# STLink_V3E_PWR.net
KiCad netlist of a schematic drawn in Altium Designer
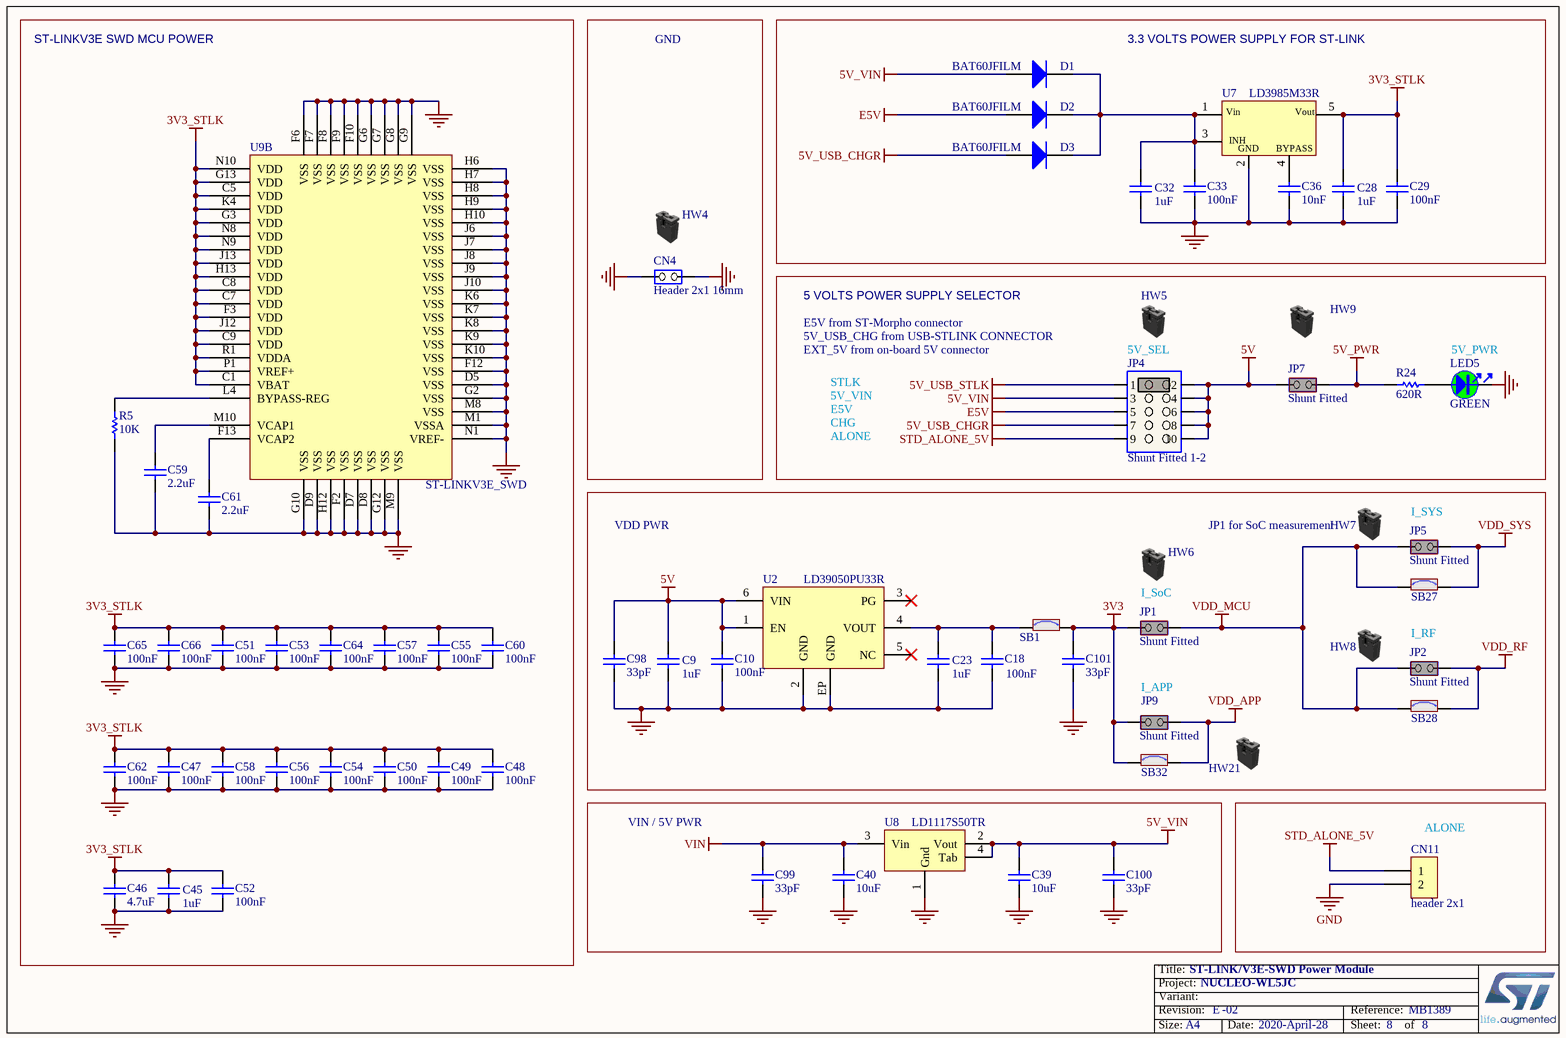
[diagram p0: STLink_V3E_PWR.SchDoc]

(export (version "E")
  (design (tool "Eeschema 10.0.6"))
  (components
    (comp (ref "C9")
      (value "1uF")
      (footprint "C0603")
      (description "Capacitor, MLCC, 1uF, 16V, X5R, 10%, 0603, T=0,8mm")
      (fields
        (field (name "INTERNAL_PART_NUMBER") "MCD-00010")
        (field (name "MANUFACTURER_PART_NUMBER") "CC0603KRX5R7BB105")
        (field (name "PROVIDED_BY") "SUBCO")
      )
      (libsource (lib "MCD_PARTS_database") (part "Capacitor"))
    )
    (comp (ref "C10")
      (value "100nF")
      (footprint "C0402")
      (description "Capacitor, MLCC, 100nF, 16V, X7R, 10%, 0402, T=0,5mm")
      (fields
        (field (name "INTERNAL_PART_NUMBER") "MCD-00102")
        (field (name "MANUFACTURER_PART_NUMBER") "CC0402KRX7R7BB104")
        (field (name "PROVIDED_BY") "SUBCO")
      )
      (libsource (lib "MCD_PARTS_database") (part "Capacitor"))
    )
    (comp (ref "C18")
      (value "100nF")
      (footprint "C0402")
      (description "Capacitor, MLCC, 100nF, 16V, X7R, 10%, 0402, T=0,5mm")
      (fields
        (field (name "INTERNAL_PART_NUMBER") "MCD-00102")
        (field (name "MANUFACTURER_PART_NUMBER") "CC0402KRX7R7BB104")
        (field (name "PROVIDED_BY") "SUBCO")
      )
      (libsource (lib "MCD_PARTS_database") (part "Capacitor"))
    )
    (comp (ref "C23")
      (value "1uF")
      (footprint "C0603")
      (description "Capacitor, MLCC, 1uF, 16V, X5R, 10%, 0603, T=0,8mm")
      (fields
        (field (name "INTERNAL_PART_NUMBER") "MCD-00010")
        (field (name "MANUFACTURER_PART_NUMBER") "CC0603KRX5R7BB105")
        (field (name "PROVIDED_BY") "SUBCO")
      )
      (libsource (lib "MCD_PARTS_database") (part "Capacitor"))
    )
    (comp (ref "C28")
      (value "1uF")
      (footprint "C0603")
      (description "Capacitor, MLCC, 1uF, 16V, X5R, 10%, 0603, T=0,8mm")
      (fields
        (field (name "INTERNAL_PART_NUMBER") "MCD-00010")
        (field (name "MANUFACTURER_PART_NUMBER") "CC0603KRX5R7BB105")
        (field (name "PROVIDED_BY") "SUBCO")
      )
      (libsource (lib "MCD_PARTS_database") (part "Capacitor"))
    )
    (comp (ref "C29")
      (value "100nF")
      (footprint "C0402")
      (description "Capacitor, MLCC, 100nF, 16V, X7R, 10%, 0402, T=0,5mm")
      (fields
        (field (name "INTERNAL_PART_NUMBER") "MCD-00102")
        (field (name "MANUFACTURER_PART_NUMBER") "CC0402KRX7R7BB104")
        (field (name "PROVIDED_BY") "SUBCO")
      )
      (libsource (lib "MCD_PARTS_database") (part "Capacitor"))
    )
    (comp (ref "C32")
      (value "1uF")
      (footprint "C0603")
      (description "Capacitor, MLCC, 1uF, 16V, X5R, 10%, 0603, T=0,8mm")
      (fields
        (field (name "INTERNAL_PART_NUMBER") "MCD-00010")
        (field (name "MANUFACTURER_PART_NUMBER") "CC0603KRX5R7BB105")
        (field (name "PROVIDED_BY") "SUBCO")
      )
      (libsource (lib "MCD_PARTS_database") (part "Capacitor"))
    )
    (comp (ref "C33")
      (value "100nF")
      (footprint "C0402")
      (description "Capacitor, MLCC, 100nF, 16V, X7R, 10%, 0402, T=0,5mm")
      (fields
        (field (name "INTERNAL_PART_NUMBER") "MCD-00102")
        (field (name "MANUFACTURER_PART_NUMBER") "CC0402KRX7R7BB104")
        (field (name "PROVIDED_BY") "SUBCO")
      )
      (libsource (lib "MCD_PARTS_database") (part "Capacitor"))
    )
    (comp (ref "C36")
      (value "10nF")
      (footprint "C0402")
      (description "Capacitor, MLCC, 10nF, 16V, X7R, 10%, 0402, T=0.5mm")
      (fields
        (field (name "INTERNAL_PART_NUMBER") "MCD-00011")
        (field (name "MANUFACTURER_PART_NUMBER") "CC0402KRX7R7BB103")
        (field (name "PROVIDED_BY") "SUBCO")
      )
      (libsource (lib "MCD_PARTS_database") (part "Capacitor"))
    )
    (comp (ref "C39")
      (value "10uF")
      (footprint "C0805")
      (description "Capacitor, MLCC, 10uF, 25V, X5R, 10%, 0805, T=0,85mm")
      (fields
        (field (name "INTERNAL_PART_NUMBER") "MCD-00014")
        (field (name "MANUFACTURER_PART_NUMBER") "CC0805KRX5R8BB106")
        (field (name "PROVIDED_BY") "SUBCO")
      )
      (libsource (lib "MCD_PARTS_database") (part "Capacitor"))
    )
    (comp (ref "C40")
      (value "10uF")
      (footprint "C0805")
      (description "Capacitor, MLCC, 10uF, 25V, X5R, 10%, 0805, T=0,85mm")
      (fields
        (field (name "INTERNAL_PART_NUMBER") "MCD-00014")
        (field (name "MANUFACTURER_PART_NUMBER") "CC0805KRX5R8BB106")
        (field (name "PROVIDED_BY") "SUBCO")
      )
      (libsource (lib "MCD_PARTS_database") (part "Capacitor"))
    )
    (comp (ref "C45")
      (value "1uF")
      (footprint "C0603")
      (description "Capacitor, MLCC, 1uF, 16V, X5R, 10%, 0603, T=0,8mm")
      (fields
        (field (name "INTERNAL_PART_NUMBER") "MCD-00010")
        (field (name "MANUFACTURER_PART_NUMBER") "CC0603KRX5R7BB105")
        (field (name "PROVIDED_BY") "SUBCO")
      )
      (libsource (lib "MCD_PARTS_database") (part "Capacitor"))
    )
    (comp (ref "C46")
      (value "4.7uF")
      (footprint "C0603")
      (description "Capacitor, MLCC, 4.7uF, 16V, X5R, 10%, 0603, T=0.8mm")
      (fields
        (field (name "INTERNAL_PART_NUMBER") "MCD-00009")
        (field (name "MANUFACTURER_PART_NUMBER") "CC0603KRX5R7BB475")
        (field (name "PROVIDED_BY") "SUBCO")
      )
      (libsource (lib "MCD_PARTS_database") (part "Capacitor"))
    )
    (comp (ref "C47")
      (value "100nF")
      (footprint "C0402")
      (description "Capacitor, MLCC, 100nF, 16V, X7R, 10%, 0402, T=0,5mm")
      (fields
        (field (name "INTERNAL_PART_NUMBER") "MCD-00102")
        (field (name "MANUFACTURER_PART_NUMBER") "CC0402KRX7R7BB104")
        (field (name "PROVIDED_BY") "SUBCO")
      )
      (libsource (lib "MCD_PARTS_database") (part "Capacitor"))
    )
    (comp (ref "C48")
      (value "100nF")
      (footprint "C0402")
      (description "Capacitor, MLCC, 100nF, 16V, X7R, 10%, 0402, T=0,5mm")
      (fields
        (field (name "INTERNAL_PART_NUMBER") "MCD-00102")
        (field (name "MANUFACTURER_PART_NUMBER") "CC0402KRX7R7BB104")
        (field (name "PROVIDED_BY") "SUBCO")
      )
      (libsource (lib "MCD_PARTS_database") (part "Capacitor"))
    )
    (comp (ref "C49")
      (value "100nF")
      (footprint "C0402")
      (description "Capacitor, MLCC, 100nF, 16V, X7R, 10%, 0402, T=0,5mm")
      (fields
        (field (name "INTERNAL_PART_NUMBER") "MCD-00102")
        (field (name "MANUFACTURER_PART_NUMBER") "CC0402KRX7R7BB104")
        (field (name "PROVIDED_BY") "SUBCO")
      )
      (libsource (lib "MCD_PARTS_database") (part "Capacitor"))
    )
    (comp (ref "C50")
      (value "100nF")
      (footprint "C0402")
      (description "Capacitor, MLCC, 100nF, 16V, X7R, 10%, 0402, T=0,5mm")
      (fields
        (field (name "INTERNAL_PART_NUMBER") "MCD-00102")
        (field (name "MANUFACTURER_PART_NUMBER") "CC0402KRX7R7BB104")
        (field (name "PROVIDED_BY") "SUBCO")
      )
      (libsource (lib "MCD_PARTS_database") (part "Capacitor"))
    )
    (comp (ref "C51")
      (value "100nF")
      (footprint "C0402")
      (description "Capacitor, MLCC, 100nF, 16V, X7R, 10%, 0402, T=0,5mm")
      (fields
        (field (name "INTERNAL_PART_NUMBER") "MCD-00102")
        (field (name "MANUFACTURER_PART_NUMBER") "CC0402KRX7R7BB104")
        (field (name "PROVIDED_BY") "SUBCO")
      )
      (libsource (lib "MCD_PARTS_database") (part "Capacitor"))
    )
    (comp (ref "C52")
      (value "100nF")
      (footprint "C0402")
      (description "Capacitor, MLCC, 100nF, 16V, X7R, 10%, 0402, T=0,5mm")
      (fields
        (field (name "INTERNAL_PART_NUMBER") "MCD-00102")
        (field (name "MANUFACTURER_PART_NUMBER") "CC0402KRX7R7BB104")
        (field (name "PROVIDED_BY") "SUBCO")
      )
      (libsource (lib "MCD_PARTS_database") (part "Capacitor"))
    )
    (comp (ref "C53")
      (value "100nF")
      (footprint "C0402")
      (description "Capacitor, MLCC, 100nF, 16V, X7R, 10%, 0402, T=0,5mm")
      (fields
        (field (name "INTERNAL_PART_NUMBER") "MCD-00102")
        (field (name "MANUFACTURER_PART_NUMBER") "CC0402KRX7R7BB104")
        (field (name "PROVIDED_BY") "SUBCO")
      )
      (libsource (lib "MCD_PARTS_database") (part "Capacitor"))
    )
    (comp (ref "C54")
      (value "100nF")
      (footprint "C0402")
      (description "Capacitor, MLCC, 100nF, 16V, X7R, 10%, 0402, T=0,5mm")
      (fields
        (field (name "INTERNAL_PART_NUMBER") "MCD-00102")
        (field (name "MANUFACTURER_PART_NUMBER") "CC0402KRX7R7BB104")
        (field (name "PROVIDED_BY") "SUBCO")
      )
      (libsource (lib "MCD_PARTS_database") (part "Capacitor"))
    )
    (comp (ref "C55")
      (value "100nF")
      (footprint "C0402")
      (description "Capacitor, MLCC, 100nF, 16V, X7R, 10%, 0402, T=0,5mm")
      (fields
        (field (name "INTERNAL_PART_NUMBER") "MCD-00102")
        (field (name "MANUFACTURER_PART_NUMBER") "CC0402KRX7R7BB104")
        (field (name "PROVIDED_BY") "SUBCO")
      )
      (libsource (lib "MCD_PARTS_database") (part "Capacitor"))
    )
    (comp (ref "C56")
      (value "100nF")
      (footprint "C0402")
      (description "Capacitor, MLCC, 100nF, 16V, X7R, 10%, 0402, T=0,5mm")
      (fields
        (field (name "INTERNAL_PART_NUMBER") "MCD-00102")
        (field (name "MANUFACTURER_PART_NUMBER") "CC0402KRX7R7BB104")
        (field (name "PROVIDED_BY") "SUBCO")
      )
      (libsource (lib "MCD_PARTS_database") (part "Capacitor"))
    )
    (comp (ref "C57")
      (value "100nF")
      (footprint "C0402")
      (description "Capacitor, MLCC, 100nF, 16V, X7R, 10%, 0402, T=0,5mm")
      (fields
        (field (name "INTERNAL_PART_NUMBER") "MCD-00102")
        (field (name "MANUFACTURER_PART_NUMBER") "CC0402KRX7R7BB104")
        (field (name "PROVIDED_BY") "SUBCO")
      )
      (libsource (lib "MCD_PARTS_database") (part "Capacitor"))
    )
    (comp (ref "C58")
      (value "100nF")
      (footprint "C0402")
      (description "Capacitor, MLCC, 100nF, 16V, X7R, 10%, 0402, T=0,5mm")
      (fields
        (field (name "INTERNAL_PART_NUMBER") "MCD-00102")
        (field (name "MANUFACTURER_PART_NUMBER") "CC0402KRX7R7BB104")
        (field (name "PROVIDED_BY") "SUBCO")
      )
      (libsource (lib "MCD_PARTS_database") (part "Capacitor"))
    )
    (comp (ref "C59")
      (value "2.2uF")
      (footprint "C0603")
      (description "Capacitor, MLCC, 2.2uF, 10V, X5R, 10%, 0603, T=0,8mm")
      (fields
        (field (name "INTERNAL_PART_NUMBER") "MCD-00012")
        (field (name "MANUFACTURER_PART_NUMBER") "CC0603KRX5R6BB225")
        (field (name "PROVIDED_BY") "SUBCO")
      )
      (libsource (lib "MCD_PARTS_database") (part "Capacitor"))
    )
    (comp (ref "C60")
      (value "100nF")
      (footprint "C0402")
      (description "Capacitor, MLCC, 100nF, 16V, X7R, 10%, 0402, T=0,5mm")
      (fields
        (field (name "INTERNAL_PART_NUMBER") "MCD-00102")
        (field (name "MANUFACTURER_PART_NUMBER") "CC0402KRX7R7BB104")
        (field (name "PROVIDED_BY") "SUBCO")
      )
      (libsource (lib "MCD_PARTS_database") (part "Capacitor"))
    )
    (comp (ref "C61")
      (value "2.2uF")
      (footprint "C0603")
      (description "Capacitor, MLCC, 2.2uF, 10V, X5R, 10%, 0603, T=0,8mm")
      (fields
        (field (name "INTERNAL_PART_NUMBER") "MCD-00012")
        (field (name "MANUFACTURER_PART_NUMBER") "CC0603KRX5R6BB225")
        (field (name "PROVIDED_BY") "SUBCO")
      )
      (libsource (lib "MCD_PARTS_database") (part "Capacitor"))
    )
    (comp (ref "C62")
      (value "100nF")
      (footprint "C0402")
      (description "Capacitor, MLCC, 100nF, 16V, X7R, 10%, 0402, T=0,5mm")
      (fields
        (field (name "INTERNAL_PART_NUMBER") "MCD-00102")
        (field (name "MANUFACTURER_PART_NUMBER") "CC0402KRX7R7BB104")
        (field (name "PROVIDED_BY") "SUBCO")
      )
      (libsource (lib "MCD_PARTS_database") (part "Capacitor"))
    )
    (comp (ref "C64")
      (value "100nF")
      (footprint "C0402")
      (description "Capacitor, MLCC, 100nF, 16V, X7R, 10%, 0402, T=0,5mm")
      (fields
        (field (name "INTERNAL_PART_NUMBER") "MCD-00102")
        (field (name "MANUFACTURER_PART_NUMBER") "CC0402KRX7R7BB104")
        (field (name "PROVIDED_BY") "SUBCO")
      )
      (libsource (lib "MCD_PARTS_database") (part "Capacitor"))
    )
    (comp (ref "C65")
      (value "100nF")
      (footprint "C0402")
      (description "Capacitor, MLCC, 100nF, 16V, X7R, 10%, 0402, T=0,5mm")
      (fields
        (field (name "INTERNAL_PART_NUMBER") "MCD-00102")
        (field (name "MANUFACTURER_PART_NUMBER") "CC0402KRX7R7BB104")
        (field (name "PROVIDED_BY") "SUBCO")
      )
      (libsource (lib "MCD_PARTS_database") (part "Capacitor"))
    )
    (comp (ref "C66")
      (value "100nF")
      (footprint "C0402")
      (description "Capacitor, MLCC, 100nF, 16V, X7R, 10%, 0402, T=0,5mm")
      (fields
        (field (name "INTERNAL_PART_NUMBER") "MCD-00102")
        (field (name "MANUFACTURER_PART_NUMBER") "CC0402KRX7R7BB104")
        (field (name "PROVIDED_BY") "SUBCO")
      )
      (libsource (lib "MCD_PARTS_database") (part "Capacitor"))
    )
    (comp (ref "C98")
      (value "33pF")
      (footprint "C0402")
      (description "Capacitor, MLCC, 33pF, 50V, NPO, +/-2%, 0402, T=0,5mm")
      (fields
        (field (name "INTERNAL_PART_NUMBER") "MCD-01784")
        (field (name "MANUFACTURER_PART_NUMBER") "CC0402GRNPO9BN330")
        (field (name "PROVIDED_BY") "SUBCO")
      )
      (libsource (lib "MCD_PARTS_database") (part "Capacitor"))
    )
    (comp (ref "C99")
      (value "33pF")
      (footprint "C0402")
      (description "Capacitor, MLCC, 33pF, 50V, NPO, +/-2%, 0402, T=0,5mm")
      (fields
        (field (name "INTERNAL_PART_NUMBER") "MCD-01784")
        (field (name "MANUFACTURER_PART_NUMBER") "CC0402GRNPO9BN330")
        (field (name "PROVIDED_BY") "SUBCO")
      )
      (libsource (lib "MCD_PARTS_database") (part "Capacitor"))
    )
    (comp (ref "C100")
      (value "33pF")
      (footprint "C0402")
      (description "Capacitor, MLCC, 33pF, 50V, NPO, +/-2%, 0402, T=0,5mm")
      (fields
        (field (name "INTERNAL_PART_NUMBER") "MCD-01784")
        (field (name "MANUFACTURER_PART_NUMBER") "CC0402GRNPO9BN330")
        (field (name "PROVIDED_BY") "SUBCO")
      )
      (libsource (lib "MCD_PARTS_database") (part "Capacitor"))
    )
    (comp (ref "C101")
      (value "33pF")
      (footprint "C0402")
      (description "Capacitor, MLCC, 33pF, 50V, NPO, +/-2%, 0402, T=0,5mm")
      (fields
        (field (name "INTERNAL_PART_NUMBER") "MCD-01784")
        (field (name "MANUFACTURER_PART_NUMBER") "CC0402GRNPO9BN330")
        (field (name "PROVIDED_BY") "SUBCO")
      )
      (libsource (lib "MCD_PARTS_database") (part "Capacitor"))
    )
    (comp (ref "CN4")
      (value "Header 2x1 16mm")
      (footprint "CON_SAMTEC_TSW-102-09-X-S")
      (description "Header, 2x1, 2,54mm, VR, TH, Height 5.84mm/10.16mm")
      (fields
        (field (name "INTERNAL_PART_NUMBER") "MCD-00214")
        (field (name "MANUFACTURER_PART_NUMBER") "TSW-102-09-x-S")
        (field (name "PROVIDED_BY") "SUBCO")
      )
      (libsource (lib "MCD_PARTS_database") (part "Jumper_Header 2x1"))
    )
    (comp (ref "CN11")
      (value "header 2x1")
      (footprint "CON_988-JIUBABA_PHFS25-11-02-G0B115-T-1")
      (description "Header, 2x1, 2.54mm, VR, TH, Height 6mm/3mm")
      (fields
        (field (name "INTERNAL_PART_NUMBER") "MCD-00314")
        (field (name "MANUFACTURER_PART_NUMBER") "PHFS25-11-02-G0B115-T-1")
        (field (name "PROVIDED_BY") "SUBCO")
      )
      (libsource (lib "MCD_PARTS_database") (part "Header 2x1"))
    )
    (comp (ref "D1")
      (value "BAT60JFILM")
      (footprint "DIO_SOD323")
      (fields
        (field (name "INTERNAL_PART_NUMBER") "MCD-00034")
        (field (name "MANUFACTURER") "STMICROELECTRONICS")
        (field (name "BMS_PART_NUMBER") "9151097")
        (field (name "PROVIDED_BY") "SUBCO with ST control")
      )
      (libsource (lib "MCD_PARTS_database") (part "BAT60JFILM"))
    )
    (comp (ref "D2")
      (value "BAT60JFILM")
      (footprint "DIO_SOD323")
      (fields
        (field (name "INTERNAL_PART_NUMBER") "MCD-00034")
        (field (name "MANUFACTURER") "STMICROELECTRONICS")
        (field (name "BMS_PART_NUMBER") "9151097")
        (field (name "PROVIDED_BY") "SUBCO with ST control")
      )
      (libsource (lib "MCD_PARTS_database") (part "BAT60JFILM"))
    )
    (comp (ref "D3")
      (value "BAT60JFILM")
      (footprint "DIO_SOD323")
      (fields
        (field (name "INTERNAL_PART_NUMBER") "MCD-00034")
        (field (name "MANUFACTURER") "STMICROELECTRONICS")
        (field (name "BMS_PART_NUMBER") "9151097")
        (field (name "PROVIDED_BY") "SUBCO with ST control")
      )
      (libsource (lib "MCD_PARTS_database") (part "BAT60JFILM"))
    )
    (comp (ref "HW4")
      (value "~")
      (description "SHUNT 2.54mm BLACK")
      (fields
        (field (name "INTERNAL_PART_NUMBER") "MCD-00043")
        (field (name "MANUFACTURER_PART_NUMBER") "SNT-100-BK-G")
        (field (name "PROVIDED_BY") "SUBCO")
      )
      (libsource (lib "MCD_PARTS_database") (part "Shunt Black 2.54mm"))
    )
    (comp (ref "HW5")
      (value "~")
      (description "SHUNT 2.54mm BLACK")
      (fields
        (field (name "INTERNAL_PART_NUMBER") "MCD-00043")
        (field (name "MANUFACTURER_PART_NUMBER") "SNT-100-BK-G")
        (field (name "PROVIDED_BY") "SUBCO")
      )
      (libsource (lib "MCD_PARTS_database") (part "Shunt Black 2.54mm"))
    )
    (comp (ref "HW6")
      (value "~")
      (description "SHUNT 2.54mm BLACK")
      (fields
        (field (name "INTERNAL_PART_NUMBER") "MCD-00043")
        (field (name "MANUFACTURER_PART_NUMBER") "SNT-100-BK-G")
        (field (name "PROVIDED_BY") "SUBCO")
      )
      (libsource (lib "MCD_PARTS_database") (part "Shunt Black 2.54mm"))
    )
    (comp (ref "HW7")
      (value "~")
      (description "SHUNT 2.54mm BLACK")
      (fields
        (field (name "INTERNAL_PART_NUMBER") "MCD-00043")
        (field (name "MANUFACTURER_PART_NUMBER") "SNT-100-BK-G")
        (field (name "PROVIDED_BY") "SUBCO")
      )
      (libsource (lib "MCD_PARTS_database") (part "Shunt Black 2.54mm"))
    )
    (comp (ref "HW8")
      (value "~")
      (description "SHUNT 2.54mm BLACK")
      (fields
        (field (name "INTERNAL_PART_NUMBER") "MCD-00043")
        (field (name "MANUFACTURER_PART_NUMBER") "SNT-100-BK-G")
        (field (name "PROVIDED_BY") "SUBCO")
      )
      (libsource (lib "MCD_PARTS_database") (part "Shunt Black 2.54mm"))
    )
    (comp (ref "HW9")
      (value "~")
      (description "SHUNT 2.54mm BLACK")
      (fields
        (field (name "INTERNAL_PART_NUMBER") "MCD-00043")
        (field (name "MANUFACTURER_PART_NUMBER") "SNT-100-BK-G")
        (field (name "PROVIDED_BY") "SUBCO")
      )
      (libsource (lib "MCD_PARTS_database") (part "Shunt Black 2.54mm"))
    )
    (comp (ref "HW21")
      (value "~")
      (description "SHUNT 2.54mm BLACK")
      (fields
        (field (name "INTERNAL_PART_NUMBER") "MCD-00043")
        (field (name "MANUFACTURER_PART_NUMBER") "SNT-100-BK-G")
        (field (name "PROVIDED_BY") "SUBCO")
      )
      (libsource (lib "MCD_PARTS_database") (part "Shunt Black 2.54mm"))
    )
    (comp (ref "JP1")
      (value "Shunt Fitted")
      (footprint "CON_SAMTEC_TSW-102-07-G-S")
      (description "Header, 2x1, 2,54mm, VR, TH, Height 5.84mm/2.54mm - Shunt Fitted by default")
      (fields
        (field (name "INTERNAL_PART_NUMBER") "MCD-00683")
        (field (name "MANUFACTURER_PART_NUMBER") "TSW-102-07-x-S")
        (field (name "PROVIDED_BY") "SUBCO")
      )
      (libsource (lib "MCD_PARTS_database") (part "Jumper_Header 2x1 Fitted"))
    )
    (comp (ref "JP2")
      (value "Shunt Fitted")
      (footprint "CON_SAMTEC_TSW-102-07-G-S")
      (description "Header, 2x1, 2,54mm, VR, TH, Height 5.84mm/2.54mm - Shunt Fitted by default")
      (fields
        (field (name "INTERNAL_PART_NUMBER") "MCD-00683")
        (field (name "MANUFACTURER_PART_NUMBER") "TSW-102-07-x-S")
        (field (name "PROVIDED_BY") "SUBCO")
      )
      (libsource (lib "MCD_PARTS_database") (part "Jumper_Header 2x1 Fitted"))
    )
    (comp (ref "JP4")
      (value "Shunt Fitted 1-2")
      (footprint "CON_SAMTEC_TSW-105-07-X-D")
      (description "Header, 5x2, 2,54mm, VR, TH, Height 5.84mm/2.54mm - Shunt Fitted 1-2")
      (fields
        (field (name "INTERNAL_PART_NUMBER") "MCD-01203")
        (field (name "MANUFACTURER_PART_NUMBER") "TSW-105-07-x-D")
        (field (name "PROVIDED_BY") "SUBCO")
      )
      (libsource (lib "MCD_PARTS_database") (part "Jumper_Header 5x2 Fitted 1-2"))
    )
    (comp (ref "JP5")
      (value "Shunt Fitted")
      (footprint "CON_SAMTEC_TSW-102-07-G-S")
      (description "Header, 2x1, 2,54mm, VR, TH, Height 5.84mm/2.54mm - Shunt Fitted by default")
      (fields
        (field (name "INTERNAL_PART_NUMBER") "MCD-00683")
        (field (name "MANUFACTURER_PART_NUMBER") "TSW-102-07-x-S")
        (field (name "PROVIDED_BY") "SUBCO")
      )
      (libsource (lib "MCD_PARTS_database") (part "Jumper_Header 2x1 Fitted"))
    )
    (comp (ref "JP7")
      (value "Shunt Fitted")
      (footprint "CON_SAMTEC_TSW-102-07-G-S")
      (description "Header, 2x1, 2,54mm, VR, TH, Height 5.84mm/2.54mm - Shunt Fitted by default")
      (fields
        (field (name "INTERNAL_PART_NUMBER") "MCD-00683")
        (field (name "MANUFACTURER_PART_NUMBER") "TSW-102-07-x-S")
        (field (name "PROVIDED_BY") "SUBCO")
      )
      (libsource (lib "MCD_PARTS_database") (part "Jumper_Header 2x1 Fitted"))
    )
    (comp (ref "JP9")
      (value "Shunt Fitted")
      (footprint "CON_SAMTEC_TSW-102-07-G-S")
      (description "Header, 2x1, 2,54mm, VR, TH, Height 5.84mm/2.54mm - Shunt Fitted by default")
      (fields
        (field (name "INTERNAL_PART_NUMBER") "MCD-00683")
        (field (name "MANUFACTURER_PART_NUMBER") "TSW-102-07-x-S")
        (field (name "PROVIDED_BY") "SUBCO")
      )
      (libsource (lib "MCD_PARTS_database") (part "Jumper_Header 2x1 Fitted"))
    )
    (comp (ref "LED5")
      (value "GREEN")
      (footprint "LED_0603_OSRAM_LG-Q396-PS-35_GREEN_1A2K_H0P4")
      (description "LED Green, 0603 SMD, Forward Voltage Typ=2V, Max=2.5V")
      (fields
        (field (name "INTERNAL_PART_NUMBER") "MCD-00588")
        (field (name "MANUFACTURER_PART_NUMBER") "LG Q396-PS-35")
        (field (name "PROVIDED_BY") "SUBCO")
      )
      (libsource (lib "MCD_PARTS_database") (part "LED_green"))
    )
    (comp (ref "R5")
      (value "10K")
      (footprint "R0402")
      (description "Resistor,10K,0402,1%,1/16W")
      (fields
        (field (name "INTERNAL_PART_NUMBER") "MCD-00053")
        (field (name "MANUFACTURER_PART_NUMBER") "RC0402FR-0710KL")
        (field (name "PROVIDED_BY") "SUBCO")
      )
      (libsource (lib "MCD_PARTS_database") (part "Resistor"))
    )
    (comp (ref "R24")
      (value "620R")
      (footprint "R0402")
      (description "Resistor,620R,0402,1%,1/16W")
      (fields
        (field (name "INTERNAL_PART_NUMBER") "MCD-00499")
        (field (name "MANUFACTURER_PART_NUMBER") "RC0402FR-07620RL")
        (field (name "PROVIDED_BY") "SUBCO")
      )
      (libsource (lib "MCD_PARTS_database") (part "Resistor"))
    )
    (comp (ref "SB1")
      (value "~")
      (footprint "SOLDER-BRIDGE_R0603-0R")
      (description "Solder Bridge ON")
      (fields
        (field (name "INTERNAL_PART_NUMBER") "MCD-00071")
        (field (name "MANUFACTURER_PART_NUMBER") "RC0603JR-070RL")
        (field (name "PROVIDED_BY") "SUBCO")
      )
      (libsource (lib "MCD_PARTS_database") (part "SB_ON"))
    )
    (comp (ref "SB27")
      (value "~")
      (footprint "SOLDER-BRIDGE_R0603-0R")
      (description "Solder Bridge ON")
      (fields
        (field (name "INTERNAL_PART_NUMBER") "MCD-00071")
        (field (name "MANUFACTURER_PART_NUMBER") "RC0603JR-070RL")
        (field (name "PROVIDED_BY") "SUBCO")
      )
      (libsource (lib "MCD_PARTS_database") (part "SB_ON"))
    )
    (comp (ref "SB28")
      (value "~")
      (footprint "SOLDER-BRIDGE_R0603-0R")
      (description "Solder Bridge ON")
      (fields
        (field (name "INTERNAL_PART_NUMBER") "MCD-00071")
        (field (name "MANUFACTURER_PART_NUMBER") "RC0603JR-070RL")
        (field (name "PROVIDED_BY") "SUBCO")
      )
      (libsource (lib "MCD_PARTS_database") (part "SB_ON"))
    )
    (comp (ref "SB32")
      (value "~")
      (footprint "SOLDER-BRIDGE_R0603-0R")
      (description "Solder Bridge ON")
      (fields
        (field (name "INTERNAL_PART_NUMBER") "MCD-00071")
        (field (name "MANUFACTURER_PART_NUMBER") "RC0603JR-070RL")
        (field (name "PROVIDED_BY") "SUBCO")
      )
      (libsource (lib "MCD_PARTS_database") (part "SB_ON"))
    )
    (comp (ref "U2")
      (value "LD39050PU33R")
      (footprint "ICC_DFN6-EPAD_3X3_P095")
      (description "Low quiescent current and low noise voltage regulators")
      (fields
        (field (name "INTERNAL_PART_NUMBER") "MCD-00215")
        (field (name "MANUFACTURER") "STMICROELECTRONICS")
        (field (name "PROVIDED_BY") "SUBCO with ST control")
      )
      (libsource (lib "MCD_PARTS_database") (part "LD39050PU33R"))
    )
    (comp (ref "U7")
      (value "LD3985M33R")
      (footprint "REG_SOT23-5L")
      (description "Ultra low drop-low noise BiCMOS voltage, regulators low ESR capacitors compatible")
      (fields
        (field (name "INTERNAL_PART_NUMBER") "MCD-00086")
        (field (name "MANUFACTURER") "STMICROELECTRONICS")
        (field (name "PROVIDED_BY") "SUBCO with ST control")
      )
      (libsource (lib "MCD_PARTS_database") (part "LD3985M33R"))
    )
    (comp (ref "U8")
      (value "LD1117S50TR")
      (footprint "REG_SOT223-TAB")
      (description "IC REG LDO 5V 0.8A SOT223")
      (fields
        (field (name "INTERNAL_PART_NUMBER") "MCD-00088")
        (field (name "MANUFACTURER") "STMICROELECTRONICS")
        (field (name "PROVIDED_BY") "SUBCO with ST control")
      )
      (libsource (lib "MCD_PARTS_database") (part "LD1117S50TR"))
    )
    (comp (ref "U9")
      (value "ST-LINKV3E_SWD")
      (footprint "ICC_UFBGA201_176+25_10X10_P065")
      (description "STM32F723IEK  (STM32F7) BGA176")
      (fields
        (field (name "INTERNAL_PART_NUMBER") "MCD-00596")
        (field (name "MANUFACTURER_PART_NUMBER") "STM32F723IEK6")
        (field (name "PROVIDED_BY") "SUBCO with ST control")
      )
      (libsource (lib "MCD_PARTS_database") (part "ST-LINKV3E_SWD"))
    )
  )
  (nets
    (net (code "1") (name "3V3") (class "Default")
      (node (ref "C101") (pin "2") (pinfunction "2_2") (pintype "passive"))
      (node (ref "JP1") (pin "1") (pinfunction "COMMON_1") (pintype "passive"))
      (node (ref "JP9") (pin "1") (pinfunction "COMMON_1") (pintype "passive"))
      (node (ref "SB1") (pin "2") (pinfunction "2_2") (pintype "passive"))
      (node (ref "SB32") (pin "1") (pinfunction "1_1") (pintype "passive"))
    )
    (net (code "2") (name "3V3_STLK") (class "Default")
      (node (ref "C28") (pin "2") (pinfunction "2_2") (pintype "passive"))
      (node (ref "C29") (pin "2") (pinfunction "2_2") (pintype "passive"))
      (node (ref "C45") (pin "2") (pinfunction "2_2") (pintype "passive"))
      (node (ref "C46") (pin "2") (pinfunction "2_2") (pintype "passive"))
      (node (ref "C47") (pin "2") (pinfunction "2_2") (pintype "passive"))
      (node (ref "C48") (pin "2") (pinfunction "2_2") (pintype "passive"))
      (node (ref "C49") (pin "2") (pinfunction "2_2") (pintype "passive"))
      (node (ref "C50") (pin "2") (pinfunction "2_2") (pintype "passive"))
      (node (ref "C51") (pin "2") (pinfunction "2_2") (pintype "passive"))
      (node (ref "C52") (pin "2") (pinfunction "2_2") (pintype "passive"))
      (node (ref "C53") (pin "2") (pinfunction "2_2") (pintype "passive"))
      (node (ref "C54") (pin "2") (pinfunction "2_2") (pintype "passive"))
      (node (ref "C55") (pin "2") (pinfunction "2_2") (pintype "passive"))
      (node (ref "C56") (pin "2") (pinfunction "2_2") (pintype "passive"))
      (node (ref "C57") (pin "2") (pinfunction "2_2") (pintype "passive"))
      (node (ref "C58") (pin "2") (pinfunction "2_2") (pintype "passive"))
      (node (ref "C60") (pin "2") (pinfunction "2_2") (pintype "passive"))
      (node (ref "C62") (pin "2") (pinfunction "2_2") (pintype "passive"))
      (node (ref "C64") (pin "2") (pinfunction "2_2") (pintype "passive"))
      (node (ref "C65") (pin "2") (pinfunction "2_2") (pintype "passive"))
      (node (ref "C66") (pin "2") (pinfunction "2_2") (pintype "passive"))
      (node (ref "U7") (pin "5") (pinfunction "Vout_5") (pintype "passive"))
      (node (ref "U9") (pin "C1") (pinfunction "VBAT_C1") (pintype "passive"))
      (node (ref "U9") (pin "C5") (pinfunction "VDD_C5") (pintype "passive"))
      (node (ref "U9") (pin "C7") (pinfunction "VDD_C7") (pintype "passive"))
      (node (ref "U9") (pin "C8") (pinfunction "VDD_C8") (pintype "passive"))
      (node (ref "U9") (pin "C9") (pinfunction "VDD_C9") (pintype "passive"))
      (node (ref "U9") (pin "F3") (pinfunction "VDD_F3") (pintype "passive"))
      (node (ref "U9") (pin "G13") (pinfunction "VDD_G13") (pintype "passive"))
      (node (ref "U9") (pin "G3") (pinfunction "VDD_G3") (pintype "passive"))
      (node (ref "U9") (pin "H13") (pinfunction "VDD_H13") (pintype "passive"))
      (node (ref "U9") (pin "J12") (pinfunction "VDD_J12") (pintype "passive"))
      (node (ref "U9") (pin "J13") (pinfunction "VDD_J13") (pintype "passive"))
      (node (ref "U9") (pin "K4") (pinfunction "VDD_K4") (pintype "passive"))
      (node (ref "U9") (pin "N10") (pinfunction "VDD_N10") (pintype "passive"))
      (node (ref "U9") (pin "N8") (pinfunction "VDD_N8") (pintype "passive"))
      (node (ref "U9") (pin "N9") (pinfunction "VDD_N9") (pintype "passive"))
      (node (ref "U9") (pin "P1") (pinfunction "VREF+_P1") (pintype "passive"))
      (node (ref "U9") (pin "R1") (pinfunction "VDDA_R1") (pintype "passive"))
    )
    (net (code "3") (name "5V") (class "Default")
      (node (ref "C10") (pin "2") (pinfunction "2_2") (pintype "passive"))
      (node (ref "C9") (pin "2") (pinfunction "2_2") (pintype "passive"))
      (node (ref "C98") (pin "2") (pinfunction "2_2") (pintype "passive"))
      (node (ref "JP4") (pin "10") (pinfunction "10_10") (pintype "passive"))
      (node (ref "JP4") (pin "2") (pinfunction "2_2") (pintype "passive"))
      (node (ref "JP4") (pin "4") (pinfunction "4_4") (pintype "passive"))
      (node (ref "JP4") (pin "6") (pinfunction "6_6") (pintype "passive"))
      (node (ref "JP4") (pin "8") (pinfunction "8_8") (pintype "passive"))
      (node (ref "JP7") (pin "1") (pinfunction "COMMON_1") (pintype "passive"))
      (node (ref "U2") (pin "1") (pinfunction "EN_1") (pintype "passive"))
      (node (ref "U2") (pin "6") (pinfunction "VIN_6") (pintype "passive"))
    )
    (net (code "4") (name "5V_PWR") (class "Default")
      (node (ref "JP7") (pin "2") (pinfunction "NO_2") (pintype "passive"))
      (node (ref "R24") (pin "1") (pinfunction "1_1") (pintype "passive"))
    )
    (net (code "5") (name "5V_USB_CHGR") (class "Default")
      (node (ref "D3") (pin "1") (pinfunction "A_1") (pintype "passive"))
      (node (ref "JP4") (pin "7") (pinfunction "7_7") (pintype "passive"))
    )
    (net (code "6") (name "5V_USB_STLK") (class "Default")
      (node (ref "JP4") (pin "1") (pinfunction "1_1") (pintype "passive"))
    )
    (net (code "7") (name "5V_VIN") (class "Default")
      (node (ref "C100") (pin "2") (pinfunction "2_2") (pintype "passive"))
      (node (ref "C39") (pin "2") (pinfunction "2_2") (pintype "passive"))
      (node (ref "D1") (pin "1") (pinfunction "A_1") (pintype "passive"))
      (node (ref "JP4") (pin "3") (pinfunction "3_3") (pintype "passive"))
      (node (ref "U8") (pin "2") (pinfunction "Vout_2") (pintype "passive"))
      (node (ref "U8") (pin "4") (pinfunction "Tab_4") (pintype "passive"))
    )
    (net (code "8") (name "E5V") (class "Default")
      (node (ref "D2") (pin "1") (pinfunction "A_1") (pintype "passive"))
      (node (ref "JP4") (pin "5") (pinfunction "5_5") (pintype "passive"))
    )
    (net (code "9") (name "GND") (class "Default")
      (node (ref "C10") (pin "1") (pinfunction "1_1") (pintype "passive"))
      (node (ref "C100") (pin "1") (pinfunction "1_1") (pintype "passive"))
      (node (ref "C101") (pin "1") (pinfunction "1_1") (pintype "passive"))
      (node (ref "C18") (pin "1") (pinfunction "1_1") (pintype "passive"))
      (node (ref "C23") (pin "1") (pinfunction "1_1") (pintype "passive"))
      (node (ref "C28") (pin "1") (pinfunction "1_1") (pintype "passive"))
      (node (ref "C29") (pin "1") (pinfunction "1_1") (pintype "passive"))
      (node (ref "C32") (pin "1") (pinfunction "1_1") (pintype "passive"))
      (node (ref "C33") (pin "1") (pinfunction "1_1") (pintype "passive"))
      (node (ref "C36") (pin "1") (pinfunction "1_1") (pintype "passive"))
      (node (ref "C39") (pin "1") (pinfunction "1_1") (pintype "passive"))
      (node (ref "C40") (pin "1") (pinfunction "1_1") (pintype "passive"))
      (node (ref "C45") (pin "1") (pinfunction "1_1") (pintype "passive"))
      (node (ref "C46") (pin "1") (pinfunction "1_1") (pintype "passive"))
      (node (ref "C47") (pin "1") (pinfunction "1_1") (pintype "passive"))
      (node (ref "C48") (pin "1") (pinfunction "1_1") (pintype "passive"))
      (node (ref "C49") (pin "1") (pinfunction "1_1") (pintype "passive"))
      (node (ref "C50") (pin "1") (pinfunction "1_1") (pintype "passive"))
      (node (ref "C51") (pin "1") (pinfunction "1_1") (pintype "passive"))
      (node (ref "C52") (pin "1") (pinfunction "1_1") (pintype "passive"))
      (node (ref "C53") (pin "1") (pinfunction "1_1") (pintype "passive"))
      (node (ref "C54") (pin "1") (pinfunction "1_1") (pintype "passive"))
      (node (ref "C55") (pin "1") (pinfunction "1_1") (pintype "passive"))
      (node (ref "C56") (pin "1") (pinfunction "1_1") (pintype "passive"))
      (node (ref "C57") (pin "1") (pinfunction "1_1") (pintype "passive"))
      (node (ref "C58") (pin "1") (pinfunction "1_1") (pintype "passive"))
      (node (ref "C59") (pin "1") (pinfunction "1_1") (pintype "passive"))
      (node (ref "C60") (pin "1") (pinfunction "1_1") (pintype "passive"))
      (node (ref "C61") (pin "1") (pinfunction "1_1") (pintype "passive"))
      (node (ref "C62") (pin "1") (pinfunction "1_1") (pintype "passive"))
      (node (ref "C64") (pin "1") (pinfunction "1_1") (pintype "passive"))
      (node (ref "C65") (pin "1") (pinfunction "1_1") (pintype "passive"))
      (node (ref "C66") (pin "1") (pinfunction "1_1") (pintype "passive"))
      (node (ref "C9") (pin "1") (pinfunction "1_1") (pintype "passive"))
      (node (ref "C98") (pin "1") (pinfunction "1_1") (pintype "passive"))
      (node (ref "C99") (pin "1") (pinfunction "1_1") (pintype "passive"))
      (node (ref "CN11") (pin "2") (pinfunction "2_2") (pintype "passive"))
      (node (ref "CN4") (pin "1") (pinfunction "COMMON_1") (pintype "passive"))
      (node (ref "CN4") (pin "2") (pinfunction "NO_2") (pintype "passive"))
      (node (ref "LED5") (pin "2") (pintype "passive"))
      (node (ref "R5") (pin "1") (pinfunction "1_1") (pintype "passive"))
      (node (ref "U2") (pin "2") (pinfunction "GND_2") (pintype "passive"))
      (node (ref "U2") (pin "EP") (pinfunction "GND_EP") (pintype "passive"))
      (node (ref "U7") (pin "2") (pinfunction "GND_2") (pintype "passive"))
      (node (ref "U8") (pin "1") (pinfunction "Gnd_1") (pintype "passive"))
      (node (ref "U9") (pin "D5") (pinfunction "VSS_D5") (pintype "passive"))
      (node (ref "U9") (pin "D7") (pinfunction "VSS_D7") (pintype "passive"))
      (node (ref "U9") (pin "D8") (pinfunction "VSS_D8") (pintype "passive"))
      (node (ref "U9") (pin "D9") (pinfunction "VSS_D9") (pintype "passive"))
      (node (ref "U9") (pin "F10") (pinfunction "VSS_F10") (pintype "passive"))
      (node (ref "U9") (pin "F12") (pinfunction "VSS_F12") (pintype "passive"))
      (node (ref "U9") (pin "F2") (pinfunction "VSS_F2") (pintype "passive"))
      (node (ref "U9") (pin "F6") (pinfunction "VSS_F6") (pintype "passive"))
      (node (ref "U9") (pin "F7") (pinfunction "VSS_F7") (pintype "passive"))
      (node (ref "U9") (pin "F8") (pinfunction "VSS_F8") (pintype "passive"))
      (node (ref "U9") (pin "F9") (pinfunction "VSS_F9") (pintype "passive"))
      (node (ref "U9") (pin "G10") (pinfunction "VSS_G10") (pintype "passive"))
      (node (ref "U9") (pin "G12") (pinfunction "VSS_G12") (pintype "passive"))
      (node (ref "U9") (pin "G2") (pinfunction "VSS_G2") (pintype "passive"))
      (node (ref "U9") (pin "G6") (pinfunction "VSS_G6") (pintype "passive"))
      (node (ref "U9") (pin "G7") (pinfunction "VSS_G7") (pintype "passive"))
      (node (ref "U9") (pin "G8") (pinfunction "VSS_G8") (pintype "passive"))
      (node (ref "U9") (pin "G9") (pinfunction "VSS_G9") (pintype "passive"))
      (node (ref "U9") (pin "H10") (pinfunction "VSS_H10") (pintype "passive"))
      (node (ref "U9") (pin "H12") (pinfunction "VSS_H12") (pintype "passive"))
      (node (ref "U9") (pin "H6") (pinfunction "VSS_H6") (pintype "passive"))
      (node (ref "U9") (pin "H7") (pinfunction "VSS_H7") (pintype "passive"))
      (node (ref "U9") (pin "H8") (pinfunction "VSS_H8") (pintype "passive"))
      (node (ref "U9") (pin "H9") (pinfunction "VSS_H9") (pintype "passive"))
      (node (ref "U9") (pin "J10") (pinfunction "VSS_J10") (pintype "passive"))
      (node (ref "U9") (pin "J6") (pinfunction "VSS_J6") (pintype "passive"))
      (node (ref "U9") (pin "J7") (pinfunction "VSS_J7") (pintype "passive"))
      (node (ref "U9") (pin "J8") (pinfunction "VSS_J8") (pintype "passive"))
      (node (ref "U9") (pin "J9") (pinfunction "VSS_J9") (pintype "passive"))
      (node (ref "U9") (pin "K10") (pinfunction "VSS_K10") (pintype "passive"))
      (node (ref "U9") (pin "K6") (pinfunction "VSS_K6") (pintype "passive"))
      (node (ref "U9") (pin "K7") (pinfunction "VSS_K7") (pintype "passive"))
      (node (ref "U9") (pin "K8") (pinfunction "VSS_K8") (pintype "passive"))
      (node (ref "U9") (pin "K9") (pinfunction "VSS_K9") (pintype "passive"))
      (node (ref "U9") (pin "M1") (pinfunction "VSSA_M1") (pintype "passive"))
      (node (ref "U9") (pin "M8") (pinfunction "VSS_M8") (pintype "passive"))
      (node (ref "U9") (pin "M9") (pinfunction "VSS_M9") (pintype "passive"))
      (node (ref "U9") (pin "N1") (pinfunction "VREF-_N1") (pintype "passive"))
    )
    (net (code "10") (name "Net-(D1-K)") (class "Default")
      (node (ref "C32") (pin "2") (pinfunction "2_2") (pintype "passive"))
      (node (ref "C33") (pin "2") (pinfunction "2_2") (pintype "passive"))
      (node (ref "D1") (pin "2") (pinfunction "K_2") (pintype "passive"))
      (node (ref "D2") (pin "2") (pinfunction "K_2") (pintype "passive"))
      (node (ref "D3") (pin "2") (pinfunction "K_2") (pintype "passive"))
      (node (ref "U7") (pin "1") (pinfunction "Vin_1") (pintype "passive"))
      (node (ref "U7") (pin "3") (pinfunction "CE_3") (pintype "passive"))
    )
    (net (code "11") (name "Net-(LED5-Pad1)") (class "Default")
      (node (ref "LED5") (pin "1") (pintype "passive"))
      (node (ref "R24") (pin "2") (pinfunction "2_2") (pintype "passive"))
    )
    (net (code "12") (name "Net-(U2-VOUT)") (class "Default")
      (node (ref "C18") (pin "2") (pinfunction "2_2") (pintype "passive"))
      (node (ref "C23") (pin "2") (pinfunction "2_2") (pintype "passive"))
      (node (ref "SB1") (pin "1") (pinfunction "1_1") (pintype "passive"))
      (node (ref "U2") (pin "4") (pinfunction "VOUT_4") (pintype "passive"))
    )
    (net (code "13") (name "Net-(U7-BYPASS)") (class "Default")
      (node (ref "C36") (pin "2") (pinfunction "2_2") (pintype "passive"))
      (node (ref "U7") (pin "4") (pinfunction "BYPASS_4") (pintype "passive"))
    )
    (net (code "14") (name "Net-(U9B-BYPASS-REG)") (class "Default")
      (node (ref "R5") (pin "2") (pinfunction "2_2") (pintype "passive"))
      (node (ref "U9") (pin "L4") (pinfunction "BYPASS-REG_L4") (pintype "passive"))
    )
    (net (code "15") (name "Net-(U9B-VCAP1)") (class "Default")
      (node (ref "C59") (pin "2") (pinfunction "2_2") (pintype "passive"))
      (node (ref "U9") (pin "M10") (pinfunction "VCAP1_M10") (pintype "passive"))
    )
    (net (code "16") (name "Net-(U9B-VCAP2)") (class "Default")
      (node (ref "C61") (pin "2") (pinfunction "2_2") (pintype "passive"))
      (node (ref "U9") (pin "F13") (pinfunction "VCAP2_F13") (pintype "passive"))
    )
    (net (code "17") (name "STD_ALONE_5V") (class "Default")
      (node (ref "CN11") (pin "1") (pinfunction "1_1") (pintype "passive"))
      (node (ref "JP4") (pin "9") (pinfunction "9_9") (pintype "passive"))
    )
    (net (code "18") (name "VDD_APP") (class "Default")
      (node (ref "JP9") (pin "2") (pinfunction "NO_2") (pintype "passive"))
      (node (ref "SB32") (pin "2") (pinfunction "2_2") (pintype "passive"))
    )
    (net (code "19") (name "VDD_MCU") (class "Default")
      (node (ref "JP1") (pin "2") (pinfunction "NO_2") (pintype "passive"))
      (node (ref "JP2") (pin "1") (pinfunction "COMMON_1") (pintype "passive"))
      (node (ref "JP5") (pin "1") (pinfunction "COMMON_1") (pintype "passive"))
      (node (ref "SB27") (pin "1") (pinfunction "1_1") (pintype "passive"))
      (node (ref "SB28") (pin "1") (pinfunction "1_1") (pintype "passive"))
    )
    (net (code "20") (name "VDD_RF") (class "Default")
      (node (ref "JP2") (pin "2") (pinfunction "NO_2") (pintype "passive"))
      (node (ref "SB28") (pin "2") (pinfunction "2_2") (pintype "passive"))
    )
    (net (code "21") (name "VDD_SYS") (class "Default")
      (node (ref "JP5") (pin "2") (pinfunction "NO_2") (pintype "passive"))
      (node (ref "SB27") (pin "2") (pinfunction "2_2") (pintype "passive"))
    )
    (net (code "22") (name "VIN") (class "Default")
      (node (ref "C40") (pin "2") (pinfunction "2_2") (pintype "passive"))
      (node (ref "C99") (pin "2") (pinfunction "2_2") (pintype "passive"))
      (node (ref "U8") (pin "3") (pinfunction "Vin_3") (pintype "passive"))
    )
    (net (code "23") (name "unconnected-(U2-NC-Pad5)") (class "Default")
      (node (ref "U2") (pin "5") (pinfunction "NC_5") (pintype "passive+no_connect"))
    )
    (net (code "24") (name "unconnected-(U2-PG-Pad3)") (class "Default")
      (node (ref "U2") (pin "3") (pinfunction "PG_3") (pintype "passive+no_connect"))
    )
  )
)
